# SP1.net
KiCad netlist of a schematic drawn in EAGLE
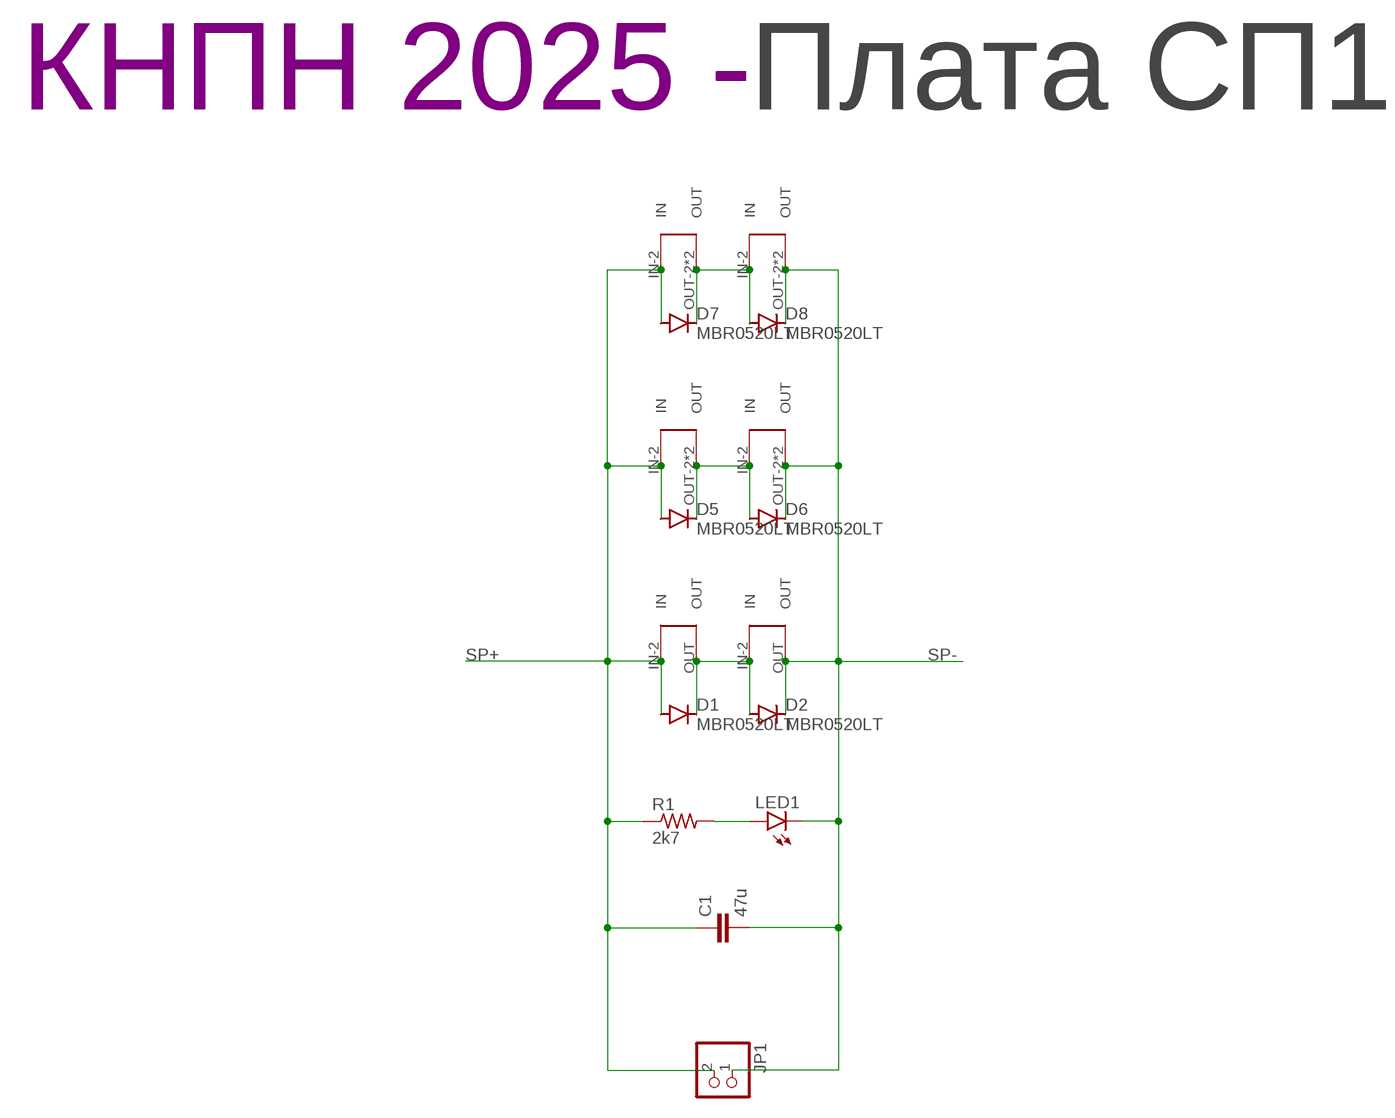
[diagram p0: schematic, sheet 1]

(export (version "E")
  (design (tool "Eeschema 10.0.6"))
  (components
    (comp (ref "C1")
      (value "47u")
      (footprint "eagle-import:C1210")
      (libsource (lib "eagle-import") (part "C-EUC1210"))
    )
    (comp (ref "D1")
      (value "MBR0520LT")
      (footprint "eagle-import:SOD123")
      (libsource (lib "eagle-import") (part "MBR0520LT"))
    )
    (comp (ref "D2")
      (value "MBR0520LT")
      (footprint "eagle-import:SOD123")
      (libsource (lib "eagle-import") (part "MBR0520LT"))
    )
    (comp (ref "D5")
      (value "MBR0520LT")
      (footprint "eagle-import:SOD123")
      (libsource (lib "eagle-import") (part "MBR0520LT"))
    )
    (comp (ref "D6")
      (value "MBR0520LT")
      (footprint "eagle-import:SOD123")
      (libsource (lib "eagle-import") (part "MBR0520LT"))
    )
    (comp (ref "D7")
      (value "MBR0520LT")
      (footprint "eagle-import:SOD123")
      (libsource (lib "eagle-import") (part "MBR0520LT"))
    )
    (comp (ref "D8")
      (value "MBR0520LT")
      (footprint "eagle-import:SOD123")
      (libsource (lib "eagle-import") (part "MBR0520LT"))
    )
    (comp (ref "JP1")
      (value "PINHD-1X2")
      (footprint "eagle-import:1X02")
      (libsource (lib "eagle-import") (part "PINHD-1X2"))
    )
    (comp (ref "LED1")
      (value "LEDCHIP-LED0603")
      (footprint "eagle-import:CHIP-LED0603")
      (libsource (lib "eagle-import") (part "LEDCHIP-LED0603"))
    )
    (comp (ref "R1")
      (value "2k7")
      (footprint "eagle-import:R0603")
      (libsource (lib "eagle-import") (part "R-US_R0603"))
    )
    (comp (ref "U$1")
      (value "SOLAR-2_1")
      (footprint "eagle-import:SOLAR_1-2")
      (libsource (lib "eagle-import") (part "SOLAR-2_1"))
    )
    (comp (ref "U$2")
      (value "SOLAR-2_1")
      (footprint "eagle-import:SOLAR_1-2")
      (libsource (lib "eagle-import") (part "SOLAR-2_1"))
    )
    (comp (ref "U$3")
      (value "Плата СП1")
      (footprint "eagle-import:LOGO")
      (libsource (lib "eagle-import") (part "LOGOPCB-{dblquote}{dblquote}"))
    )
    (comp (ref "U$5")
      (value "SOLAR-2_0")
      (footprint "eagle-import:SOLAR_0-2")
      (libsource (lib "eagle-import") (part "SOLAR-2_0"))
    )
    (comp (ref "U$6")
      (value "SOLAR-2_0")
      (footprint "eagle-import:SOLAR_0-2")
      (libsource (lib "eagle-import") (part "SOLAR-2_0"))
    )
    (comp (ref "U$7")
      (value "SOLAR-2_0")
      (footprint "eagle-import:SOLAR_0-2")
      (libsource (lib "eagle-import") (part "SOLAR-2_0"))
    )
    (comp (ref "U$8")
      (value "SOLAR-2_0")
      (footprint "eagle-import:SOLAR_0-2")
      (libsource (lib "eagle-import") (part "SOLAR-2_0"))
    )
  )
  (nets
    (net (code "1") (name "/SP+") (class "Default")
      (node (ref "C1") (pin "1") (pinfunction "1_1") (pintype "passive"))
      (node (ref "D1") (pin "A") (pinfunction "A_A") (pintype "passive"))
      (node (ref "D5") (pin "A") (pinfunction "A_A") (pintype "passive"))
      (node (ref "D7") (pin "A") (pinfunction "A_A") (pintype "passive"))
      (node (ref "JP1") (pin "2") (pinfunction "2_2") (pintype "passive"))
      (node (ref "R1") (pin "1") (pinfunction "1_1") (pintype "passive"))
      (node (ref "U$1") (pin "IN-2") (pinfunction "IN_IN-2") (pintype "bidirectional"))
      (node (ref "U$5") (pin "IN-2") (pinfunction "IN_IN-2") (pintype "bidirectional"))
      (node (ref "U$7") (pin "IN-2") (pinfunction "IN_IN-2") (pintype "bidirectional"))
    )
    (net (code "2") (name "/SP-") (class "Default")
      (node (ref "C1") (pin "2") (pinfunction "2_2") (pintype "passive"))
      (node (ref "D2") (pin "C") (pinfunction "C_C") (pintype "passive"))
      (node (ref "D6") (pin "C") (pinfunction "C_C") (pintype "passive"))
      (node (ref "D8") (pin "C") (pinfunction "C_C") (pintype "passive"))
      (node (ref "JP1") (pin "1") (pinfunction "1_1") (pintype "passive"))
      (node (ref "LED1") (pin "C") (pinfunction "C_C") (pintype "passive"))
      (node (ref "U$2") (pin "OUT") (pinfunction "OUT_OUT") (pintype "bidirectional"))
      (node (ref "U$6") (pin "OUT-2") (pinfunction "OUT_OUT-2") (pintype "bidirectional"))
      (node (ref "U$6") (pin "OUT-21") (pinfunction "OUT_OUT-21") (pintype "bidirectional"))
      (node (ref "U$8") (pin "OUT-2") (pinfunction "OUT_OUT-2") (pintype "bidirectional"))
      (node (ref "U$8") (pin "OUT-21") (pinfunction "OUT_OUT-21") (pintype "bidirectional"))
    )
    (net (code "3") (name "Net-(LED1-PadA)") (class "Default")
      (node (ref "LED1") (pin "A") (pinfunction "A_A") (pintype "passive"))
      (node (ref "R1") (pin "2") (pinfunction "2_2") (pintype "passive"))
    )
    (net (code "4") (name "Net-(U$2-IN)") (class "Default")
      (node (ref "D1") (pin "C") (pinfunction "C_C") (pintype "passive"))
      (node (ref "D2") (pin "A") (pinfunction "A_A") (pintype "passive"))
      (node (ref "U$1") (pin "OUT") (pinfunction "OUT_OUT") (pintype "bidirectional"))
      (node (ref "U$2") (pin "IN-2") (pinfunction "IN_IN-2") (pintype "bidirectional"))
    )
    (net (code "5") (name "Net-(U$6-IN)") (class "Default")
      (node (ref "D5") (pin "C") (pinfunction "C_C") (pintype "passive"))
      (node (ref "D6") (pin "A") (pinfunction "A_A") (pintype "passive"))
      (node (ref "U$5") (pin "OUT-2") (pinfunction "OUT_OUT-2") (pintype "bidirectional"))
      (node (ref "U$5") (pin "OUT-21") (pinfunction "OUT_OUT-21") (pintype "bidirectional"))
      (node (ref "U$6") (pin "IN-2") (pinfunction "IN_IN-2") (pintype "bidirectional"))
    )
    (net (code "6") (name "Net-(U$8-IN)") (class "Default")
      (node (ref "D7") (pin "C") (pinfunction "C_C") (pintype "passive"))
      (node (ref "D8") (pin "A") (pinfunction "A_A") (pintype "passive"))
      (node (ref "U$7") (pin "OUT-2") (pinfunction "OUT_OUT-2") (pintype "bidirectional"))
      (node (ref "U$7") (pin "OUT-21") (pinfunction "OUT_OUT-21") (pintype "bidirectional"))
      (node (ref "U$8") (pin "IN-2") (pinfunction "IN_IN-2") (pintype "bidirectional"))
    )
  )
)
